# flync_node.net
KiCad netlist of a schematic drawn in EAGLE
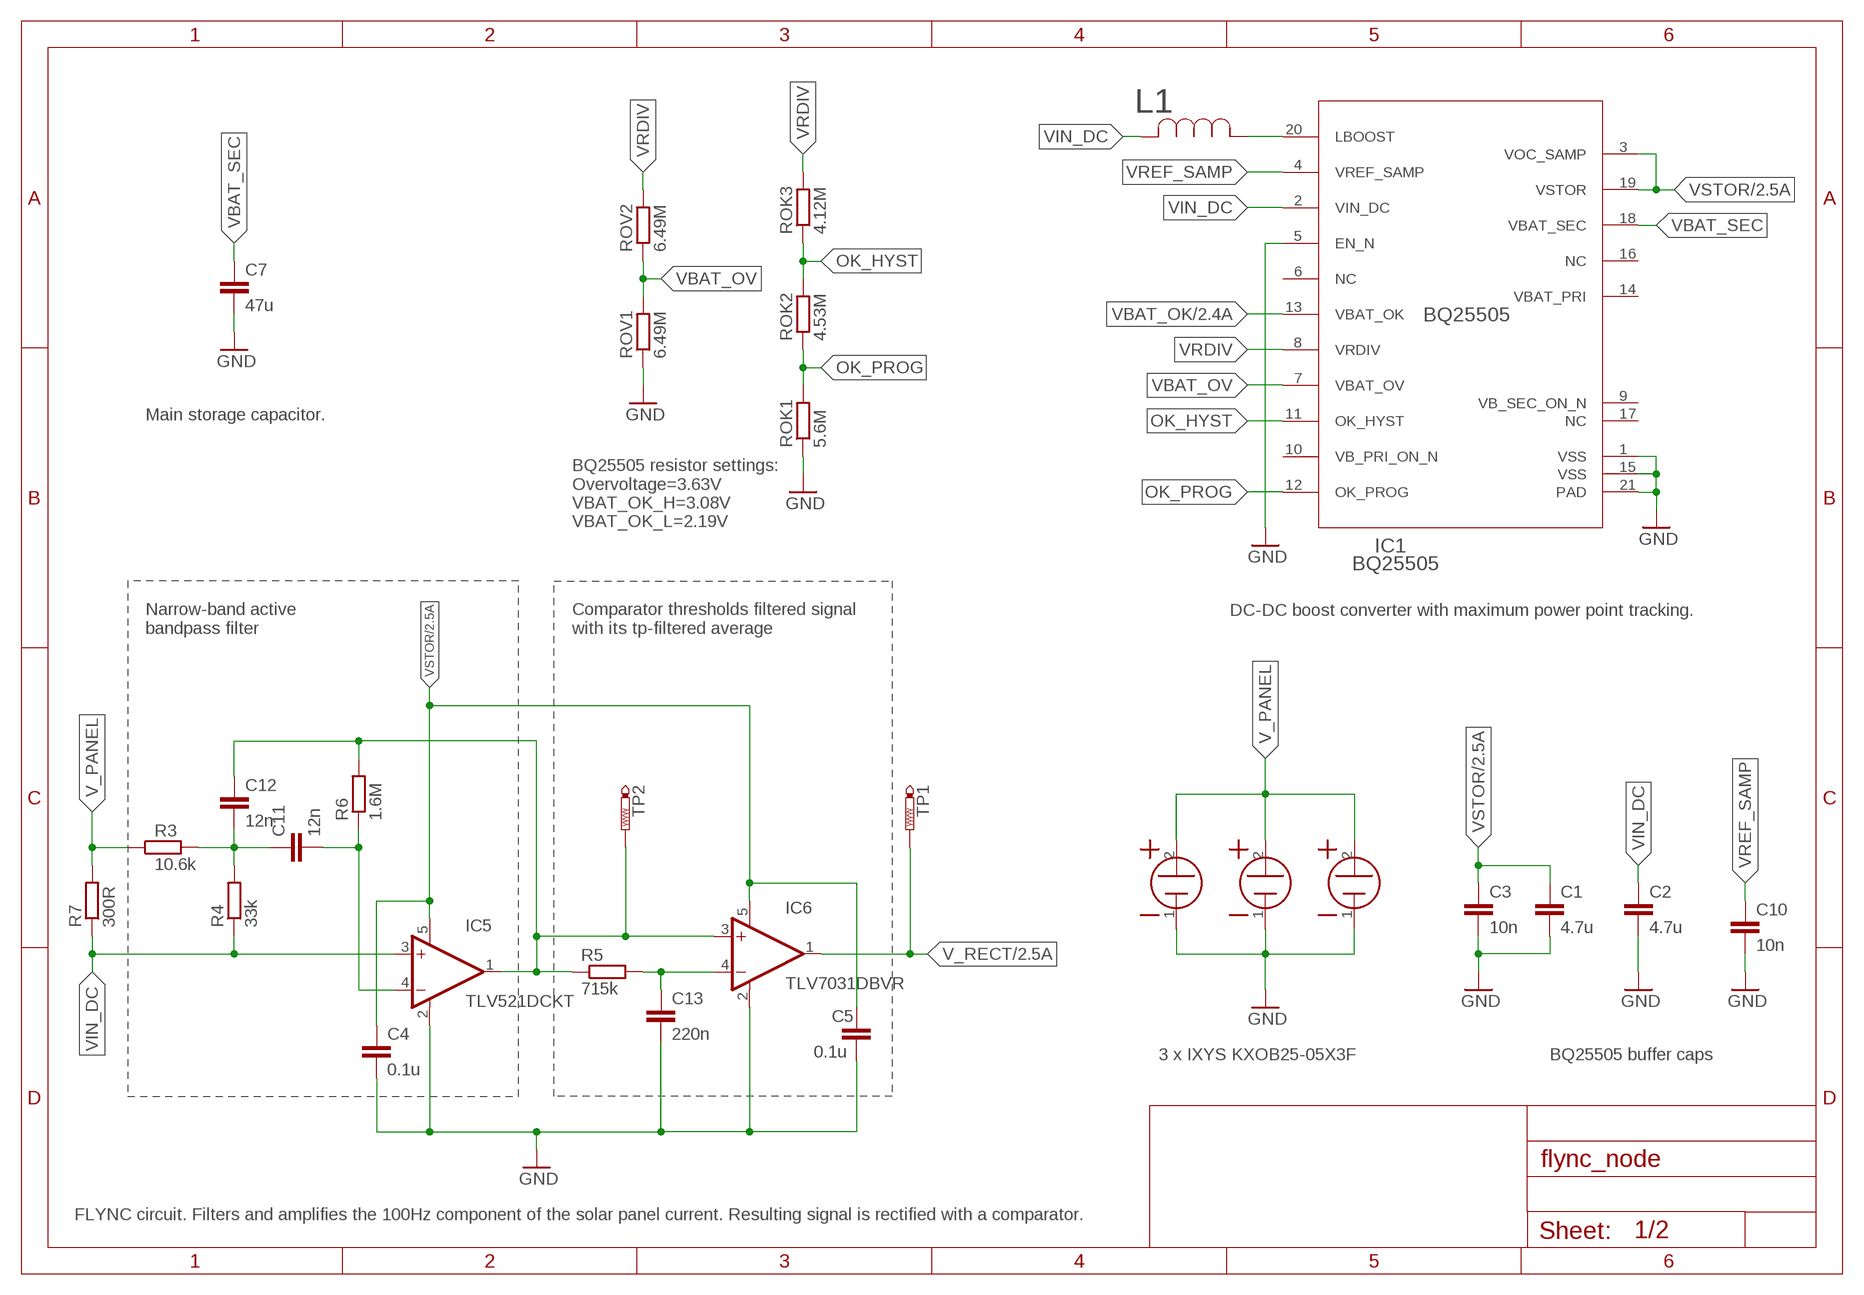
[diagram p0: schematic, sheet 1]
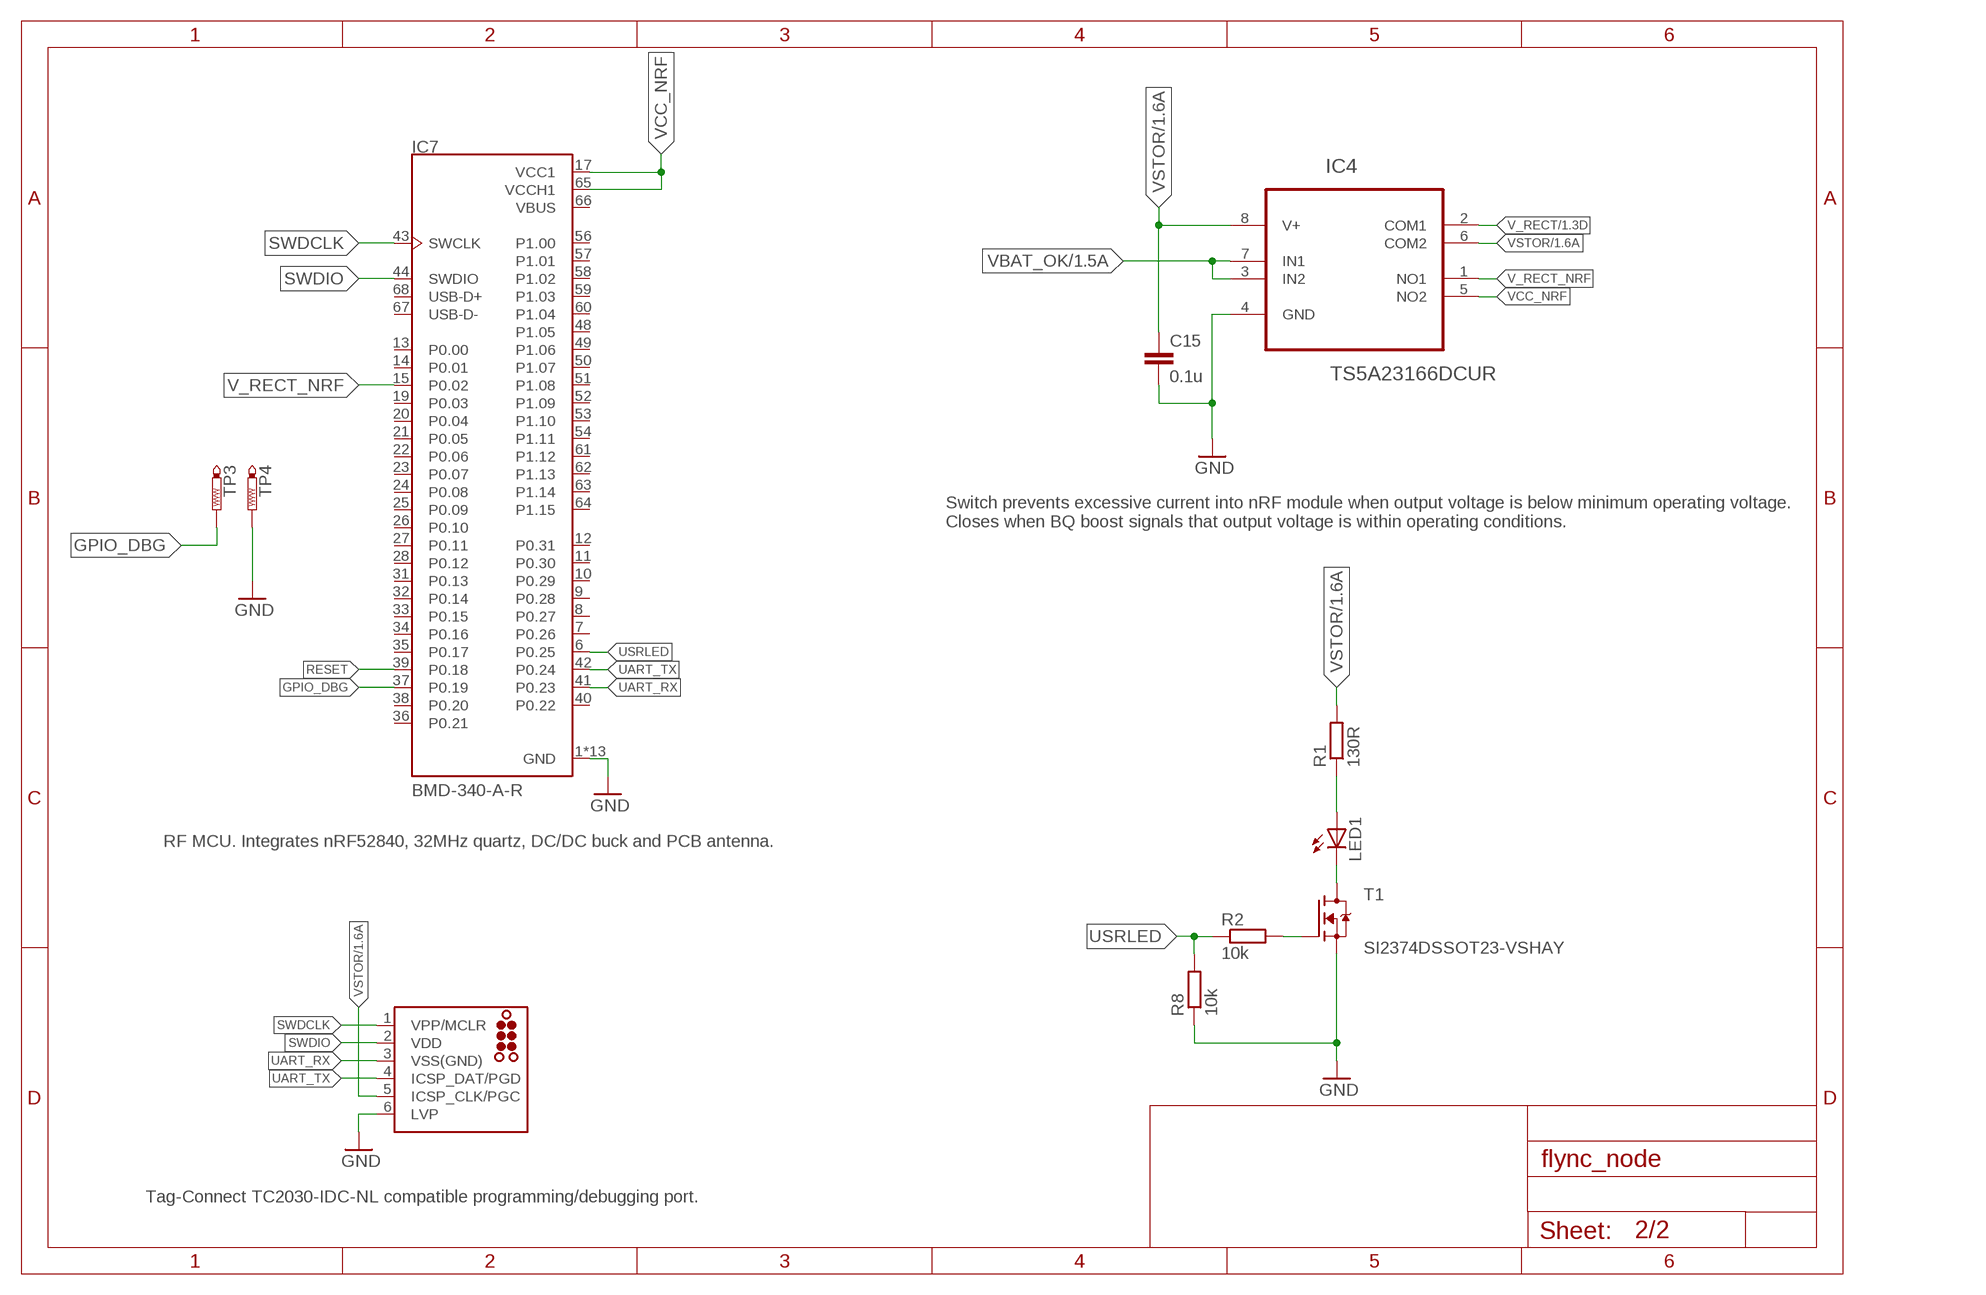
[diagram p1: schematic, sheet 2]

(export (version "E")
  (design (tool "Eeschema 10.0.6"))
  (components
    (comp (ref "C15")
      (value "0.1u")
      (footprint "eagle-import:CAPC1005X55")
      (libsource (lib "eagle-import") (part "C_SMD0402"))
    )
    (comp (ref "IC4")
      (value "TS5A23166DCUR")
      (footprint "eagle-import:SOP50P310X90-8N")
      (fields (field (name "MF") "Texas Instruments"))
      (libsource (lib "eagle-import") (part "TS5A23166DCUR"))
    )
    (comp (ref "IC7")
      (value "BMD-340-A-R")
      (footprint "eagle-import:RIGADO_BMD-340-A-R")
      (fields (field (name "MF") "Rigado"))
      (libsource (lib "eagle-import") (part "BMD-340-A-R"))
    )
    (comp (ref "J1")
      (value "TC2030-MCP-NL")
      (footprint "eagle-import:TC2030-MCP-NL")
      (libsource (lib "eagle-import") (part "TC2030-MCP-NL"))
    )
    (comp (ref "LED1")
      (value "598-8130-107FLED_0805")
      (footprint "eagle-import:LEDC2012X75")
      (libsource (lib "eagle-import") (part "598-8130-107FLED_0805"))
    )
    (comp (ref "R1")
      (value "130R")
      (footprint "eagle-import:RESC1608X55")
      (libsource (lib "eagle-import") (part "R_SMD0603"))
    )
    (comp (ref "R2")
      (value "10k")
      (footprint "eagle-import:RESC1005X40")
      (libsource (lib "eagle-import") (part "R_SMD0402"))
    )
    (comp (ref "R8")
      (value "10k")
      (footprint "eagle-import:RESC1005X40")
      (libsource (lib "eagle-import") (part "R_SMD0402"))
    )
    (comp (ref "T1")
      (value "SI2374DSSOT23-VSHAY")
      (footprint "eagle-import:SOT95P237X112-3")
      (libsource (lib "eagle-import") (part "SI2374DSSOT23-VSHAY"))
    )
    (comp (ref "TP3")
      (value "PTR1TP16SQ")
      (footprint "eagle-import:TP16SQ")
      (libsource (lib "eagle-import") (part "PTR1TP16SQ"))
    )
    (comp (ref "TP4")
      (value "PTR1TP16SQ")
      (footprint "eagle-import:TP16SQ")
      (libsource (lib "eagle-import") (part "PTR1TP16SQ"))
    )
    (comp (ref "C1")
      (value "4.7u")
      (footprint "eagle-import:CAPC1005X55")
      (libsource (lib "eagle-import") (part "C_SMD0402"))
    )
    (comp (ref "C2")
      (value "4.7u")
      (footprint "eagle-import:CAPC1005X55")
      (libsource (lib "eagle-import") (part "C_SMD0402"))
    )
    (comp (ref "C3")
      (value "10n")
      (footprint "eagle-import:CAPC1005X55")
      (libsource (lib "eagle-import") (part "C_SMD0402"))
    )
    (comp (ref "C4")
      (value "0.1u")
      (footprint "eagle-import:CAPC1005X55")
      (libsource (lib "eagle-import") (part "C_SMD0402"))
    )
    (comp (ref "C5")
      (value "0.1u")
      (footprint "eagle-import:CAPC1005X55")
      (libsource (lib "eagle-import") (part "C_SMD0402"))
    )
    (comp (ref "C7")
      (value "47u")
      (footprint "eagle-import:CAPC2012X145")
      (libsource (lib "eagle-import") (part "C_SMD0805"))
    )
    (comp (ref "C10")
      (value "10n")
      (footprint "eagle-import:CAPC1005X55")
      (libsource (lib "eagle-import") (part "C_SMD0402"))
    )
    (comp (ref "C11")
      (value "12n")
      (footprint "eagle-import:CAPC2012X145")
      (libsource (lib "eagle-import") (part "C_SMD0805"))
    )
    (comp (ref "C12")
      (value "12n")
      (footprint "eagle-import:CAPC2012X145")
      (libsource (lib "eagle-import") (part "C_SMD0805"))
    )
    (comp (ref "C13")
      (value "220n")
      (footprint "eagle-import:CAPC1005X55")
      (libsource (lib "eagle-import") (part "C_SMD0402"))
    )
    (comp (ref "H1")
      (value "IXYSKXOB25-05X3F")
      (footprint "eagle-import:IXYS23X8")
      (libsource (lib "eagle-import") (part "IXYSKXOB25-05X3F"))
    )
    (comp (ref "H2")
      (value "IXYSKXOB25-05X3F")
      (footprint "eagle-import:IXYS23X8")
      (libsource (lib "eagle-import") (part "IXYSKXOB25-05X3F"))
    )
    (comp (ref "H3")
      (value "IXYSKXOB25-05X3F")
      (footprint "eagle-import:IXYS23X8")
      (libsource (lib "eagle-import") (part "IXYSKXOB25-05X3F"))
    )
    (comp (ref "IC1")
      (value "BQ25505")
      (footprint "eagle-import:RGR0020A")
      (libsource (lib "eagle-import") (part "BQ25505"))
    )
    (comp (ref "IC5")
      (value "TLV521DCKT")
      (footprint "eagle-import:DCK5")
      (fields (field (name "COPYRIGHT") "Copyright (C) 2018 Accelerated Designs. All rights reserved"))
      (libsource (lib "eagle-import") (part "TLV521DCKT"))
    )
    (comp (ref "IC6")
      (value "TLV7031DBVR")
      (footprint "eagle-import:DBV5-L")
      (libsource (lib "eagle-import") (part "TLV7031DBVR"))
    )
    (comp (ref "L1")
      (value "LBR2518T220KIND1007_47N_TAI-L")
      (footprint "eagle-import:IND1007_47N_TAI-L")
      (fields (field (name "MANUFACTURER_PART_NUMBER") "LBR2518T220K"))
      (libsource (lib "eagle-import") (part "LBR2518T220KIND1007_47N_TAI-L"))
    )
    (comp (ref "R3")
      (value "10.6k")
      (footprint "eagle-import:RESC1005X40")
      (libsource (lib "eagle-import") (part "R_SMD0402"))
    )
    (comp (ref "R4")
      (value "33k")
      (footprint "eagle-import:RESC1005X40")
      (libsource (lib "eagle-import") (part "R_SMD0402"))
    )
    (comp (ref "R5")
      (value "715k")
      (footprint "eagle-import:RESC1005X40")
      (libsource (lib "eagle-import") (part "R_SMD0402"))
    )
    (comp (ref "R6")
      (value "1.6M")
      (footprint "eagle-import:RESC1005X40")
      (libsource (lib "eagle-import") (part "R_SMD0402"))
    )
    (comp (ref "R7")
      (value "300R")
      (footprint "eagle-import:RESC1608X55")
      (libsource (lib "eagle-import") (part "R_SMD0603"))
    )
    (comp (ref "ROK1")
      (value "5.6M")
      (footprint "eagle-import:RESC1005X40")
      (libsource (lib "eagle-import") (part "R_SMD0402"))
    )
    (comp (ref "ROK2")
      (value "4.53M")
      (footprint "eagle-import:RESC1005X40")
      (libsource (lib "eagle-import") (part "R_SMD0402"))
    )
    (comp (ref "ROK3")
      (value "4.12M")
      (footprint "eagle-import:RESC1005X40")
      (libsource (lib "eagle-import") (part "R_SMD0402"))
    )
    (comp (ref "ROV1")
      (value "6.49M")
      (footprint "eagle-import:RESC1005X40")
      (libsource (lib "eagle-import") (part "R_SMD0402"))
    )
    (comp (ref "ROV2")
      (value "6.49M")
      (footprint "eagle-import:RESC1005X40")
      (libsource (lib "eagle-import") (part "R_SMD0402"))
    )
    (comp (ref "TP1")
      (value "PTR1TP08R")
      (footprint "eagle-import:TP08R")
      (libsource (lib "eagle-import") (part "PTR1TP08R"))
    )
    (comp (ref "TP2")
      (value "PTR1TP08R")
      (footprint "eagle-import:TP08R")
      (libsource (lib "eagle-import") (part "PTR1TP08R"))
    )
  )
  (nets
    (net (code "1") (name "GND") (class "Default")
      (node (ref "C1") (pin "2") (pinfunction "2_2") (pintype "passive"))
      (node (ref "C10") (pin "2") (pinfunction "2_2") (pintype "passive"))
      (node (ref "C13") (pin "2") (pinfunction "2_2") (pintype "passive"))
      (node (ref "C15") (pin "2") (pinfunction "2_2") (pintype "passive"))
      (node (ref "C2") (pin "2") (pinfunction "2_2") (pintype "passive"))
      (node (ref "C3") (pin "2") (pinfunction "2_2") (pintype "passive"))
      (node (ref "C4") (pin "2") (pinfunction "2_2") (pintype "passive"))
      (node (ref "C5") (pin "2") (pinfunction "2_2") (pintype "passive"))
      (node (ref "C7") (pin "2") (pinfunction "2_2") (pintype "passive"))
      (node (ref "H1") (pin "1") (pinfunction "P$1_1") (pintype "power_in"))
      (node (ref "H2") (pin "1") (pinfunction "P$1_1") (pintype "power_in"))
      (node (ref "H3") (pin "1") (pinfunction "P$1_1") (pintype "power_in"))
      (node (ref "IC1") (pin "1") (pinfunction "VSS_1") (pintype "power_in"))
      (node (ref "IC1") (pin "15") (pinfunction "VSS_15") (pintype "power_in"))
      (node (ref "IC1") (pin "21") (pinfunction "PAD_21") (pintype "power_in"))
      (node (ref "IC1") (pin "5") (pinfunction "EN_N_5") (pintype "input"))
      (node (ref "IC4") (pin "4") (pinfunction "GND_4") (pintype "passive"))
      (node (ref "IC5") (pin "2") (pinfunction "V-_2") (pintype "power_in"))
      (node (ref "IC6") (pin "2") (pinfunction "V-_2") (pintype "power_in"))
      (node (ref "IC7") (pin "1") (pinfunction "GND_1") (pintype "power_in"))
      (node (ref "IC7") (pin "16") (pinfunction "GND_16") (pintype "power_in"))
      (node (ref "IC7") (pin "18") (pinfunction "GND_18") (pintype "power_in"))
      (node (ref "IC7") (pin "2") (pinfunction "GND_2") (pintype "power_in"))
      (node (ref "IC7") (pin "29") (pinfunction "GND_29") (pintype "power_in"))
      (node (ref "IC7") (pin "3") (pinfunction "GND_3") (pintype "power_in"))
      (node (ref "IC7") (pin "30") (pinfunction "GND_30") (pintype "power_in"))
      (node (ref "IC7") (pin "4") (pinfunction "GND_4") (pintype "power_in"))
      (node (ref "IC7") (pin "45") (pinfunction "GND_45") (pintype "power_in"))
      (node (ref "IC7") (pin "46") (pinfunction "GND_46") (pintype "power_in"))
      (node (ref "IC7") (pin "47") (pinfunction "GND_47") (pintype "power_in"))
      (node (ref "IC7") (pin "5") (pinfunction "GND_5") (pintype "power_in"))
      (node (ref "IC7") (pin "55") (pinfunction "GND_55") (pintype "power_in"))
      (node (ref "J1") (pin "6") (pinfunction "LVP_6") (pintype "bidirectional"))
      (node (ref "R8") (pin "1") (pinfunction "1_1") (pintype "passive"))
      (node (ref "ROK1") (pin "1") (pinfunction "1_1") (pintype "passive"))
      (node (ref "ROV1") (pin "1") (pinfunction "1_1") (pintype "passive"))
      (node (ref "T1") (pin "2") (pinfunction "S_2") (pintype "passive"))
      (node (ref "TP4") (pin "TP") (pinfunction "TP_TP") (pintype "input"))
    )
    (net (code "2") (name "GPIO_DBG") (class "Default")
      (node (ref "IC7") (pin "37") (pinfunction "P0.19_37") (pintype "bidirectional"))
      (node (ref "TP3") (pin "TP") (pinfunction "TP_TP") (pintype "input"))
    )
    (net (code "3") (name "Net-(C11-Pad1)") (class "Default")
      (node (ref "C11") (pin "1") (pinfunction "1_1") (pintype "passive"))
      (node (ref "C12") (pin "2") (pinfunction "2_2") (pintype "passive"))
      (node (ref "R3") (pin "2") (pinfunction "2_2") (pintype "passive"))
      (node (ref "R4") (pin "2") (pinfunction "2_2") (pintype "passive"))
    )
    (net (code "4") (name "Net-(IC1-LBOOST)") (class "Default")
      (node (ref "IC1") (pin "20") (pinfunction "LBOOST_20") (pintype "input"))
      (node (ref "L1") (pin "1") (pinfunction "1_1") (pintype "passive"))
    )
    (net (code "5") (name "Net-(IC5--IN)") (class "Default")
      (node (ref "C11") (pin "2") (pinfunction "2_2") (pintype "passive"))
      (node (ref "IC5") (pin "4") (pinfunction "-IN_4") (pintype "input"))
      (node (ref "R6") (pin "1") (pinfunction "1_1") (pintype "passive"))
    )
    (net (code "6") (name "Net-(IC5-OUT)") (class "Default")
      (node (ref "C12") (pin "1") (pinfunction "1_1") (pintype "passive"))
      (node (ref "IC5") (pin "1") (pinfunction "OUT_1") (pintype "output"))
      (node (ref "IC6") (pin "3") (pinfunction "+IN_3") (pintype "input"))
      (node (ref "R5") (pin "1") (pinfunction "1_1") (pintype "passive"))
      (node (ref "R6") (pin "2") (pinfunction "2_2") (pintype "passive"))
      (node (ref "TP2") (pin "TP") (pinfunction "TP_TP") (pintype "input"))
    )
    (net (code "7") (name "Net-(IC6--IN)") (class "Default")
      (node (ref "C13") (pin "1") (pinfunction "1_1") (pintype "passive"))
      (node (ref "IC6") (pin "4") (pinfunction "-IN_4") (pintype "input"))
      (node (ref "R5") (pin "2") (pinfunction "2_2") (pintype "passive"))
    )
    (net (code "8") (name "Net-(LED1-A)") (class "Default")
      (node (ref "LED1") (pin "2") (pinfunction "A_2") (pintype "passive"))
      (node (ref "R1") (pin "1") (pinfunction "1_1") (pintype "passive"))
    )
    (net (code "9") (name "Net-(LED1-C)") (class "Default")
      (node (ref "LED1") (pin "1") (pinfunction "C_1") (pintype "passive"))
      (node (ref "T1") (pin "3") (pinfunction "D_3") (pintype "passive"))
    )
    (net (code "10") (name "Net-(T1-G)") (class "Default")
      (node (ref "R2") (pin "2") (pinfunction "2_2") (pintype "passive"))
      (node (ref "T1") (pin "1") (pinfunction "G_1") (pintype "passive"))
    )
    (net (code "11") (name "OK_HYST") (class "Default")
      (node (ref "IC1") (pin "11") (pinfunction "OK_HYST_11") (pintype "input"))
      (node (ref "ROK2") (pin "2") (pinfunction "2_2") (pintype "passive"))
      (node (ref "ROK3") (pin "1") (pinfunction "1_1") (pintype "passive"))
    )
    (net (code "12") (name "OK_PROG") (class "Default")
      (node (ref "IC1") (pin "12") (pinfunction "OK_PROG_12") (pintype "input"))
      (node (ref "ROK1") (pin "2") (pinfunction "2_2") (pintype "passive"))
      (node (ref "ROK2") (pin "1") (pinfunction "1_1") (pintype "passive"))
    )
    (net (code "13") (name "RESET") (class "Default")
      (node (ref "IC7") (pin "39") (pinfunction "P0.18_39") (pintype "bidirectional"))
    )
    (net (code "14") (name "SWDCLK") (class "Default")
      (node (ref "IC7") (pin "43") (pinfunction "SWCLK_43") (pintype "input"))
      (node (ref "J1") (pin "1") (pinfunction "VPP/MCLR_1") (pintype "passive"))
    )
    (net (code "15") (name "SWDIO") (class "Default")
      (node (ref "IC7") (pin "44") (pinfunction "SWDIO_44") (pintype "bidirectional"))
      (node (ref "J1") (pin "2") (pinfunction "VDD_2") (pintype "power_in"))
    )
    (net (code "16") (name "UART_RX") (class "Default")
      (node (ref "IC7") (pin "41") (pinfunction "P0.23_41") (pintype "bidirectional"))
      (node (ref "J1") (pin "3") (pinfunction "VSS(GND)_3") (pintype "power_in"))
    )
    (net (code "17") (name "UART_TX") (class "Default")
      (node (ref "IC7") (pin "42") (pinfunction "P0.24_42") (pintype "bidirectional"))
      (node (ref "J1") (pin "4") (pinfunction "ICSP_DAT/PGD_4") (pintype "bidirectional"))
    )
    (net (code "18") (name "USRLED") (class "Default")
      (node (ref "IC7") (pin "6") (pinfunction "P0.25_6") (pintype "bidirectional"))
      (node (ref "R2") (pin "1") (pinfunction "1_1") (pintype "passive"))
      (node (ref "R8") (pin "2") (pinfunction "2_2") (pintype "passive"))
    )
    (net (code "19") (name "VBAT_OK") (class "Default")
      (node (ref "IC1") (pin "13") (pinfunction "VBAT_OK_13") (pintype "output"))
      (node (ref "IC4") (pin "3") (pinfunction "IN2_3") (pintype "input"))
      (node (ref "IC4") (pin "7") (pinfunction "IN1_7") (pintype "input"))
    )
    (net (code "20") (name "VBAT_OV") (class "Default")
      (node (ref "IC1") (pin "7") (pinfunction "VBAT_OV_7") (pintype "input"))
      (node (ref "ROV1") (pin "2") (pinfunction "2_2") (pintype "passive"))
      (node (ref "ROV2") (pin "1") (pinfunction "1_1") (pintype "passive"))
    )
    (net (code "21") (name "VBAT_PRI") (class "Default")
      (node (ref "IC1") (pin "14") (pinfunction "VBAT_PRI_14") (pintype "power_in"))
    )
    (net (code "22") (name "VBAT_SEC") (class "Default")
      (node (ref "C7") (pin "1") (pinfunction "1_1") (pintype "passive"))
      (node (ref "IC1") (pin "18") (pinfunction "VBAT_SEC_18") (pintype "power_in"))
    )
    (net (code "23") (name "VBUS") (class "Default")
      (node (ref "IC7") (pin "66") (pinfunction "VBUS_66") (pintype "power_in"))
    )
    (net (code "24") (name "VB_SEC_ON_N") (class "Default")
      (node (ref "IC1") (pin "9") (pinfunction "VB_SEC_ON_N_9") (pintype "power_in"))
    )
    (net (code "25") (name "VCC_NRF") (class "Default")
      (node (ref "IC4") (pin "5") (pinfunction "NO2_5") (pintype "bidirectional"))
      (node (ref "IC7") (pin "17") (pinfunction "VCC1_17") (pintype "power_in"))
      (node (ref "IC7") (pin "65") (pinfunction "VCCH1_65") (pintype "power_in"))
    )
    (net (code "26") (name "VIN_DC") (class "Default")
      (node (ref "C2") (pin "1") (pinfunction "1_1") (pintype "passive"))
      (node (ref "IC1") (pin "2") (pinfunction "VIN_DC_2") (pintype "power_in"))
      (node (ref "IC5") (pin "3") (pinfunction "+IN_3") (pintype "input"))
      (node (ref "L1") (pin "2") (pinfunction "2_2") (pintype "passive"))
      (node (ref "R4") (pin "1") (pinfunction "1_1") (pintype "passive"))
      (node (ref "R7") (pin "1") (pinfunction "1_1") (pintype "passive"))
    )
    (net (code "27") (name "VRDIV") (class "Default")
      (node (ref "IC1") (pin "8") (pinfunction "VRDIV_8") (pintype "output"))
      (node (ref "ROK3") (pin "2") (pinfunction "2_2") (pintype "passive"))
      (node (ref "ROV2") (pin "2") (pinfunction "2_2") (pintype "passive"))
    )
    (net (code "28") (name "VREF_SAMP") (class "Default")
      (node (ref "C10") (pin "1") (pinfunction "1_1") (pintype "passive"))
      (node (ref "IC1") (pin "4") (pinfunction "VREF_SAMP_4") (pintype "input"))
    )
    (net (code "29") (name "VSTOR") (class "Default")
      (node (ref "C1") (pin "1") (pinfunction "1_1") (pintype "passive"))
      (node (ref "C15") (pin "1") (pinfunction "1_1") (pintype "passive"))
      (node (ref "C3") (pin "1") (pinfunction "1_1") (pintype "passive"))
      (node (ref "C4") (pin "1") (pinfunction "1_1") (pintype "passive"))
      (node (ref "C5") (pin "1") (pinfunction "1_1") (pintype "passive"))
      (node (ref "IC1") (pin "19") (pinfunction "VSTOR_19") (pintype "power_in"))
      (node (ref "IC1") (pin "3") (pinfunction "VOC_SAMP_3") (pintype "input"))
      (node (ref "IC4") (pin "6") (pinfunction "COM2_6") (pintype "bidirectional"))
      (node (ref "IC4") (pin "8") (pinfunction "V+_8") (pintype "power_in"))
      (node (ref "IC5") (pin "5") (pinfunction "V+_5") (pintype "power_in"))
      (node (ref "IC6") (pin "5") (pinfunction "V+_5") (pintype "power_in"))
      (node (ref "J1") (pin "5") (pinfunction "ICSP_CLK/PGC_5") (pintype "output"))
      (node (ref "R1") (pin "2") (pinfunction "2_2") (pintype "passive"))
    )
    (net (code "30") (name "V_PANEL") (class "Default")
      (node (ref "H1") (pin "2") (pinfunction "P$2_2") (pintype "power_in"))
      (node (ref "H2") (pin "2") (pinfunction "P$2_2") (pintype "power_in"))
      (node (ref "H3") (pin "2") (pinfunction "P$2_2") (pintype "power_in"))
      (node (ref "R3") (pin "1") (pinfunction "1_1") (pintype "passive"))
      (node (ref "R7") (pin "2") (pinfunction "2_2") (pintype "passive"))
    )
    (net (code "31") (name "V_RECT") (class "Default")
      (node (ref "IC4") (pin "2") (pinfunction "COM1_2") (pintype "bidirectional"))
      (node (ref "IC6") (pin "1") (pinfunction "OUT_1") (pintype "output"))
      (node (ref "TP1") (pin "TP") (pinfunction "TP_TP") (pintype "input"))
    )
    (net (code "32") (name "V_RECT_NRF") (class "Default")
      (node (ref "IC4") (pin "1") (pinfunction "NO1_1") (pintype "bidirectional"))
      (node (ref "IC7") (pin "15") (pinfunction "P0.02_15") (pintype "bidirectional"))
    )
    (net (code "33") (name "unconnected-(IC1-NC-Pad6)") (class "Default")
      (node (ref "IC1") (pin "6") (pinfunction "NC_6") (pintype "no_connect"))
    )
    (net (code "34") (name "unconnected-(IC1-NC-Pad16)") (class "Default")
      (node (ref "IC1") (pin "16") (pinfunction "NC_16") (pintype "no_connect"))
    )
    (net (code "35") (name "unconnected-(IC1-NC-Pad17)") (class "Default")
      (node (ref "IC1") (pin "17") (pinfunction "NC_17") (pintype "no_connect"))
    )
    (net (code "36") (name "unconnected-(IC1-VB_PRI_ON_N-Pad10)") (class "Default")
      (node (ref "IC1") (pin "10") (pinfunction "VB_PRI_ON_N_10") (pintype "output"))
    )
    (net (code "37") (name "unconnected-(IC7-P0.00-Pad13)") (class "Default")
      (node (ref "IC7") (pin "13") (pinfunction "P0.00_13") (pintype "bidirectional"))
    )
    (net (code "38") (name "unconnected-(IC7-P0.01-Pad14)") (class "Default")
      (node (ref "IC7") (pin "14") (pinfunction "P0.01_14") (pintype "bidirectional"))
    )
    (net (code "39") (name "unconnected-(IC7-P0.03-Pad19)") (class "Default")
      (node (ref "IC7") (pin "19") (pinfunction "P0.03_19") (pintype "bidirectional"))
    )
    (net (code "40") (name "unconnected-(IC7-P0.04-Pad20)") (class "Default")
      (node (ref "IC7") (pin "20") (pinfunction "P0.04_20") (pintype "bidirectional"))
    )
    (net (code "41") (name "unconnected-(IC7-P0.05-Pad21)") (class "Default")
      (node (ref "IC7") (pin "21") (pinfunction "P0.05_21") (pintype "bidirectional"))
    )
    (net (code "42") (name "unconnected-(IC7-P0.06-Pad22)") (class "Default")
      (node (ref "IC7") (pin "22") (pinfunction "P0.06_22") (pintype "bidirectional"))
    )
    (net (code "43") (name "unconnected-(IC7-P0.07-Pad23)") (class "Default")
      (node (ref "IC7") (pin "23") (pinfunction "P0.07_23") (pintype "bidirectional"))
    )
    (net (code "44") (name "unconnected-(IC7-P0.08-Pad24)") (class "Default")
      (node (ref "IC7") (pin "24") (pinfunction "P0.08_24") (pintype "bidirectional"))
    )
    (net (code "45") (name "unconnected-(IC7-P0.09-Pad25)") (class "Default")
      (node (ref "IC7") (pin "25") (pinfunction "P0.09_25") (pintype "bidirectional"))
    )
    (net (code "46") (name "unconnected-(IC7-P0.10-Pad26)") (class "Default")
      (node (ref "IC7") (pin "26") (pinfunction "P0.10_26") (pintype "bidirectional"))
    )
    (net (code "47") (name "unconnected-(IC7-P0.11-Pad27)") (class "Default")
      (node (ref "IC7") (pin "27") (pinfunction "P0.11_27") (pintype "bidirectional"))
    )
    (net (code "48") (name "unconnected-(IC7-P0.12-Pad28)") (class "Default")
      (node (ref "IC7") (pin "28") (pinfunction "P0.12_28") (pintype "bidirectional"))
    )
    (net (code "49") (name "unconnected-(IC7-P0.13-Pad31)") (class "Default")
      (node (ref "IC7") (pin "31") (pinfunction "P0.13_31") (pintype "bidirectional"))
    )
    (net (code "50") (name "unconnected-(IC7-P0.14-Pad32)") (class "Default")
      (node (ref "IC7") (pin "32") (pinfunction "P0.14_32") (pintype "bidirectional"))
    )
    (net (code "51") (name "unconnected-(IC7-P0.15-Pad33)") (class "Default")
      (node (ref "IC7") (pin "33") (pinfunction "P0.15_33") (pintype "bidirectional"))
    )
    (net (code "52") (name "unconnected-(IC7-P0.16-Pad34)") (class "Default")
      (node (ref "IC7") (pin "34") (pinfunction "P0.16_34") (pintype "bidirectional"))
    )
    (net (code "53") (name "unconnected-(IC7-P0.17-Pad35)") (class "Default")
      (node (ref "IC7") (pin "35") (pinfunction "P0.17_35") (pintype "bidirectional"))
    )
    (net (code "54") (name "unconnected-(IC7-P0.20-Pad38)") (class "Default")
      (node (ref "IC7") (pin "38") (pinfunction "P0.20_38") (pintype "bidirectional"))
    )
    (net (code "55") (name "unconnected-(IC7-P0.21-Pad36)") (class "Default")
      (node (ref "IC7") (pin "36") (pinfunction "P0.21_36") (pintype "bidirectional"))
    )
    (net (code "56") (name "unconnected-(IC7-P0.22-Pad40)") (class "Default")
      (node (ref "IC7") (pin "40") (pinfunction "P0.22_40") (pintype "bidirectional"))
    )
    (net (code "57") (name "unconnected-(IC7-P0.26-Pad7)") (class "Default")
      (node (ref "IC7") (pin "7") (pinfunction "P0.26_7") (pintype "bidirectional"))
    )
    (net (code "58") (name "unconnected-(IC7-P0.27-Pad8)") (class "Default")
      (node (ref "IC7") (pin "8") (pinfunction "P0.27_8") (pintype "bidirectional"))
    )
    (net (code "59") (name "unconnected-(IC7-P0.28-Pad9)") (class "Default")
      (node (ref "IC7") (pin "9") (pinfunction "P0.28_9") (pintype "bidirectional"))
    )
    (net (code "60") (name "unconnected-(IC7-P0.29-Pad10)") (class "Default")
      (node (ref "IC7") (pin "10") (pinfunction "P0.29_10") (pintype "bidirectional"))
    )
    (net (code "61") (name "unconnected-(IC7-P0.30-Pad11)") (class "Default")
      (node (ref "IC7") (pin "11") (pinfunction "P0.30_11") (pintype "bidirectional"))
    )
    (net (code "62") (name "unconnected-(IC7-P0.31-Pad12)") (class "Default")
      (node (ref "IC7") (pin "12") (pinfunction "P0.31_12") (pintype "bidirectional"))
    )
    (net (code "63") (name "unconnected-(IC7-P1.00-Pad56)") (class "Default")
      (node (ref "IC7") (pin "56") (pinfunction "P1.00_56") (pintype "bidirectional"))
    )
    (net (code "64") (name "unconnected-(IC7-P1.01-Pad57)") (class "Default")
      (node (ref "IC7") (pin "57") (pinfunction "P1.01_57") (pintype "bidirectional"))
    )
    (net (code "65") (name "unconnected-(IC7-P1.02-Pad58)") (class "Default")
      (node (ref "IC7") (pin "58") (pinfunction "P1.02_58") (pintype "bidirectional"))
    )
    (net (code "66") (name "unconnected-(IC7-P1.03-Pad59)") (class "Default")
      (node (ref "IC7") (pin "59") (pinfunction "P1.03_59") (pintype "bidirectional"))
    )
    (net (code "67") (name "unconnected-(IC7-P1.04-Pad60)") (class "Default")
      (node (ref "IC7") (pin "60") (pinfunction "P1.04_60") (pintype "bidirectional"))
    )
    (net (code "68") (name "unconnected-(IC7-P1.05-Pad48)") (class "Default")
      (node (ref "IC7") (pin "48") (pinfunction "P1.05_48") (pintype "bidirectional"))
    )
    (net (code "69") (name "unconnected-(IC7-P1.06-Pad49)") (class "Default")
      (node (ref "IC7") (pin "49") (pinfunction "P1.06_49") (pintype "bidirectional"))
    )
    (net (code "70") (name "unconnected-(IC7-P1.07-Pad50)") (class "Default")
      (node (ref "IC7") (pin "50") (pinfunction "P1.07_50") (pintype "bidirectional"))
    )
    (net (code "71") (name "unconnected-(IC7-P1.08-Pad51)") (class "Default")
      (node (ref "IC7") (pin "51") (pinfunction "P1.08_51") (pintype "bidirectional"))
    )
    (net (code "72") (name "unconnected-(IC7-P1.09-Pad52)") (class "Default")
      (node (ref "IC7") (pin "52") (pinfunction "P1.09_52") (pintype "bidirectional"))
    )
    (net (code "73") (name "unconnected-(IC7-P1.10-Pad53)") (class "Default")
      (node (ref "IC7") (pin "53") (pinfunction "P1.10_53") (pintype "bidirectional"))
    )
    (net (code "74") (name "unconnected-(IC7-P1.11-Pad54)") (class "Default")
      (node (ref "IC7") (pin "54") (pinfunction "P1.11_54") (pintype "bidirectional"))
    )
    (net (code "75") (name "unconnected-(IC7-P1.12-Pad61)") (class "Default")
      (node (ref "IC7") (pin "61") (pinfunction "P1.12_61") (pintype "bidirectional"))
    )
    (net (code "76") (name "unconnected-(IC7-P1.13-Pad62)") (class "Default")
      (node (ref "IC7") (pin "62") (pinfunction "P1.13_62") (pintype "bidirectional"))
    )
    (net (code "77") (name "unconnected-(IC7-P1.14-Pad63)") (class "Default")
      (node (ref "IC7") (pin "63") (pinfunction "P1.14_63") (pintype "bidirectional"))
    )
    (net (code "78") (name "unconnected-(IC7-P1.15-Pad64)") (class "Default")
      (node (ref "IC7") (pin "64") (pinfunction "P1.15_64") (pintype "bidirectional"))
    )
    (net (code "79") (name "unconnected-(IC7-USB-D+-Pad68)") (class "Default")
      (node (ref "IC7") (pin "68") (pinfunction "USB-D+_68") (pintype "bidirectional"))
    )
    (net (code "80") (name "unconnected-(IC7-USB-D--Pad67)") (class "Default")
      (node (ref "IC7") (pin "67") (pinfunction "USB-D-_67") (pintype "bidirectional"))
    )
  )
)
